# hangsz_r.net
KiCad netlist of a schematic drawn in EAGLE
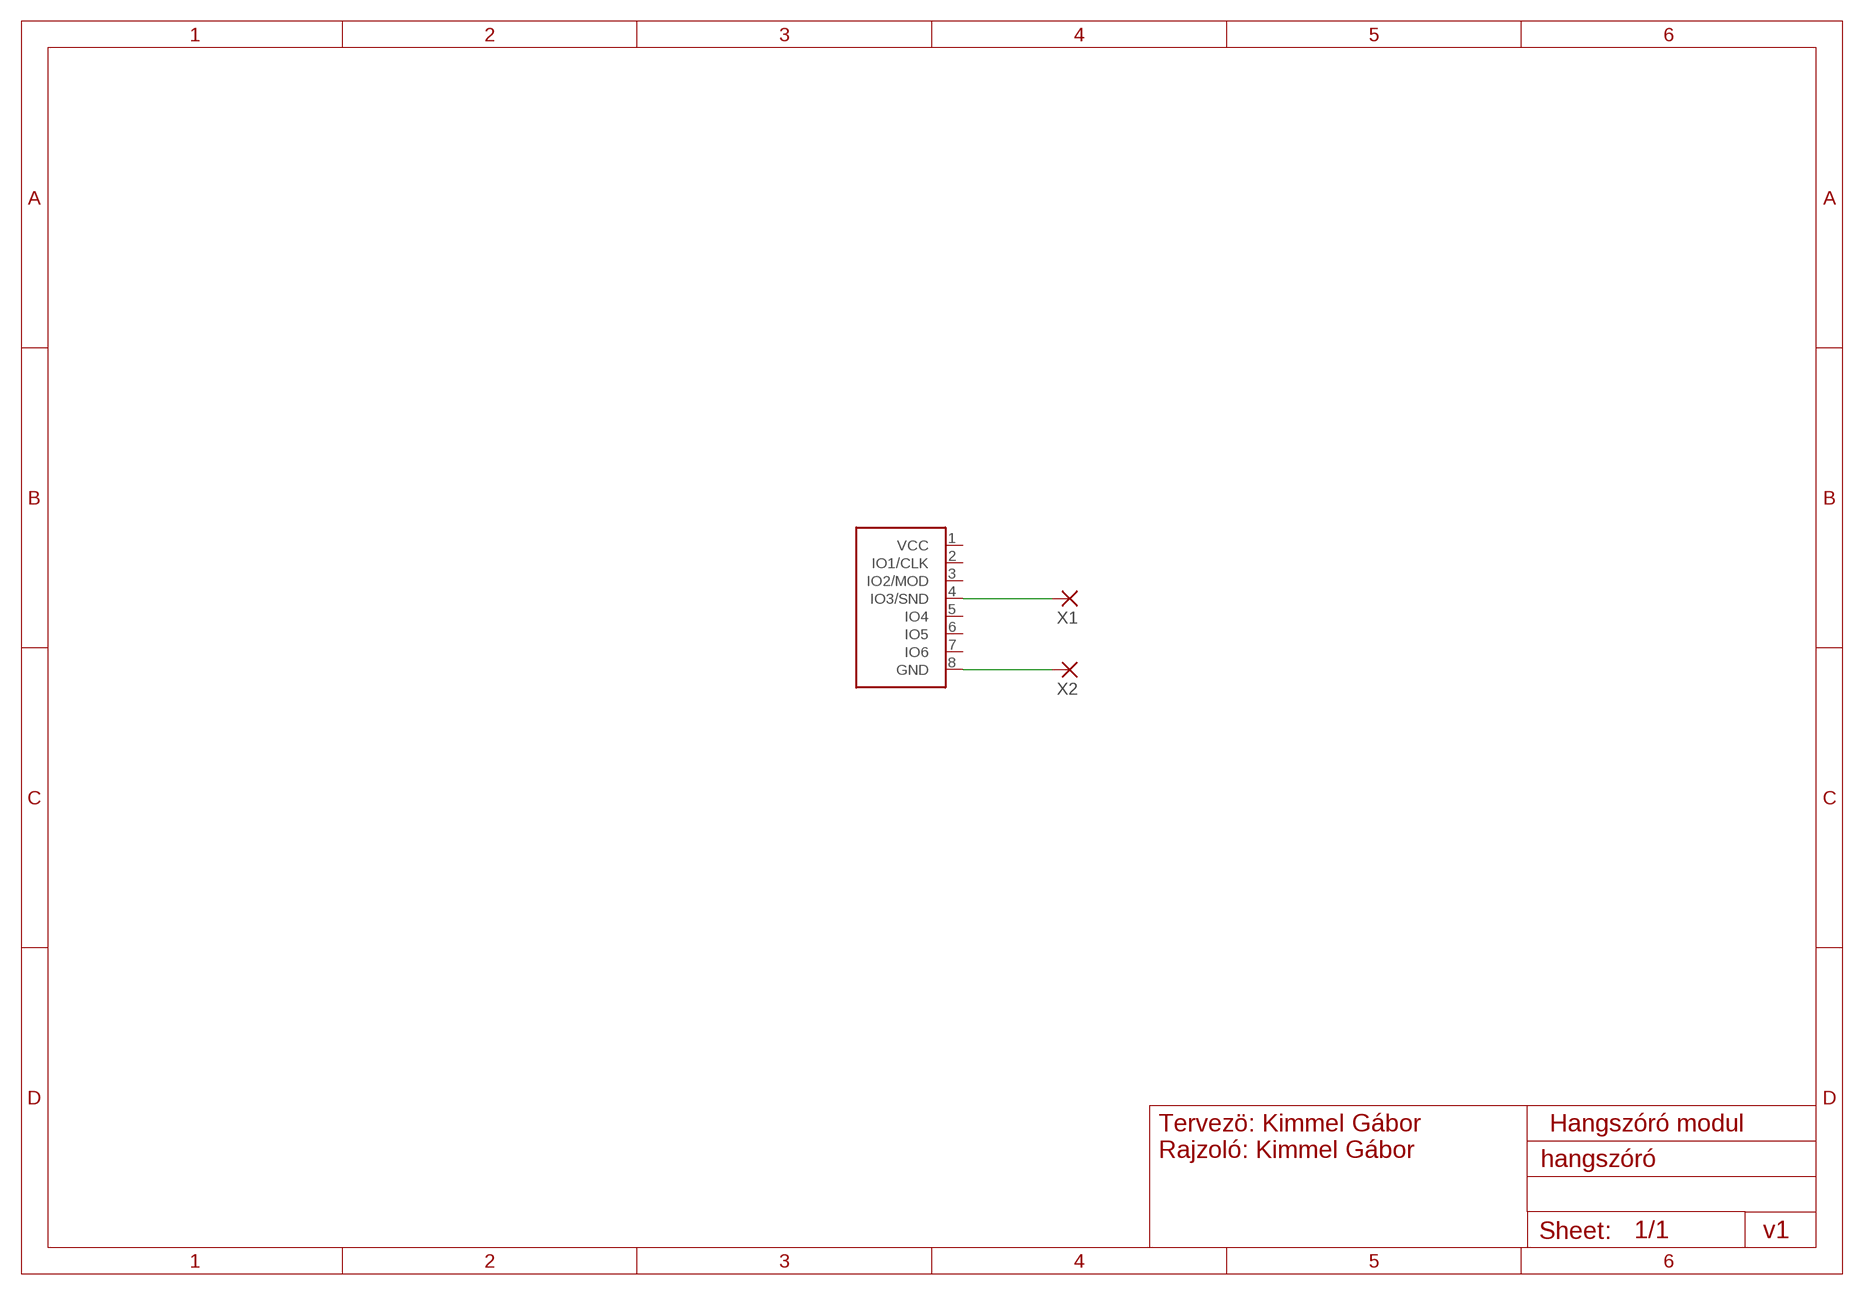
[diagram p0: schematic, sheet 1]

(export (version "E")
  (design (tool "Eeschema 10.0.6"))
  (components
    (comp (ref "U$1")
      (value "GANZ-CONNECTOR")
      (footprint "eagle-import:FE08W")
      (libsource (lib "eagle-import") (part "GANZ-CONNECTOR"))
    )
    (comp (ref "X1")
      (value "2,15/1,0")
      (footprint "eagle-import:2,15_1,0")
      (libsource (lib "eagle-import") (part "2,15/1,0"))
    )
    (comp (ref "X2")
      (value "2,15/1,0")
      (footprint "eagle-import:2,15_1,0")
      (libsource (lib "eagle-import") (part "2,15/1,0"))
    )
  )
  (nets
    (net (code "1") (name "Net-(U$1-GND)") (class "Default")
      (node (ref "U$1") (pin "8") (pinfunction "GND_8") (pintype "bidirectional"))
      (node (ref "X2") (pin "1") (pinfunction "P_1") (pintype "passive"))
    )
    (net (code "2") (name "Net-(U$1-IO3{slash}SND)") (class "Default")
      (node (ref "U$1") (pin "4") (pinfunction "IO3/SND_4") (pintype "bidirectional"))
      (node (ref "X1") (pin "1") (pinfunction "P_1") (pintype "passive"))
    )
    (net (code "3") (name "unconnected-(U$1-IO1{slash}CLK-Pad2)") (class "Default")
      (node (ref "U$1") (pin "2") (pinfunction "IO1/CLK_2") (pintype "bidirectional"))
    )
    (net (code "4") (name "unconnected-(U$1-IO2{slash}MOD-Pad3)") (class "Default")
      (node (ref "U$1") (pin "3") (pinfunction "IO2/MOD_3") (pintype "bidirectional"))
    )
    (net (code "5") (name "unconnected-(U$1-IO4-Pad5)") (class "Default")
      (node (ref "U$1") (pin "5") (pinfunction "IO4_5") (pintype "bidirectional"))
    )
    (net (code "6") (name "unconnected-(U$1-IO5-Pad6)") (class "Default")
      (node (ref "U$1") (pin "6") (pinfunction "IO5_6") (pintype "bidirectional"))
    )
    (net (code "7") (name "unconnected-(U$1-IO6-Pad7)") (class "Default")
      (node (ref "U$1") (pin "7") (pinfunction "IO6_7") (pintype "bidirectional"))
    )
    (net (code "8") (name "unconnected-(U$1-VCC-Pad1)") (class "Default")
      (node (ref "U$1") (pin "1") (pinfunction "VCC_1") (pintype "bidirectional"))
    )
  )
)
